# ProPrj_Smart_medcil_2024-12-30.net
KiCad netlist of a schematic drawn in EasyEDA Pro
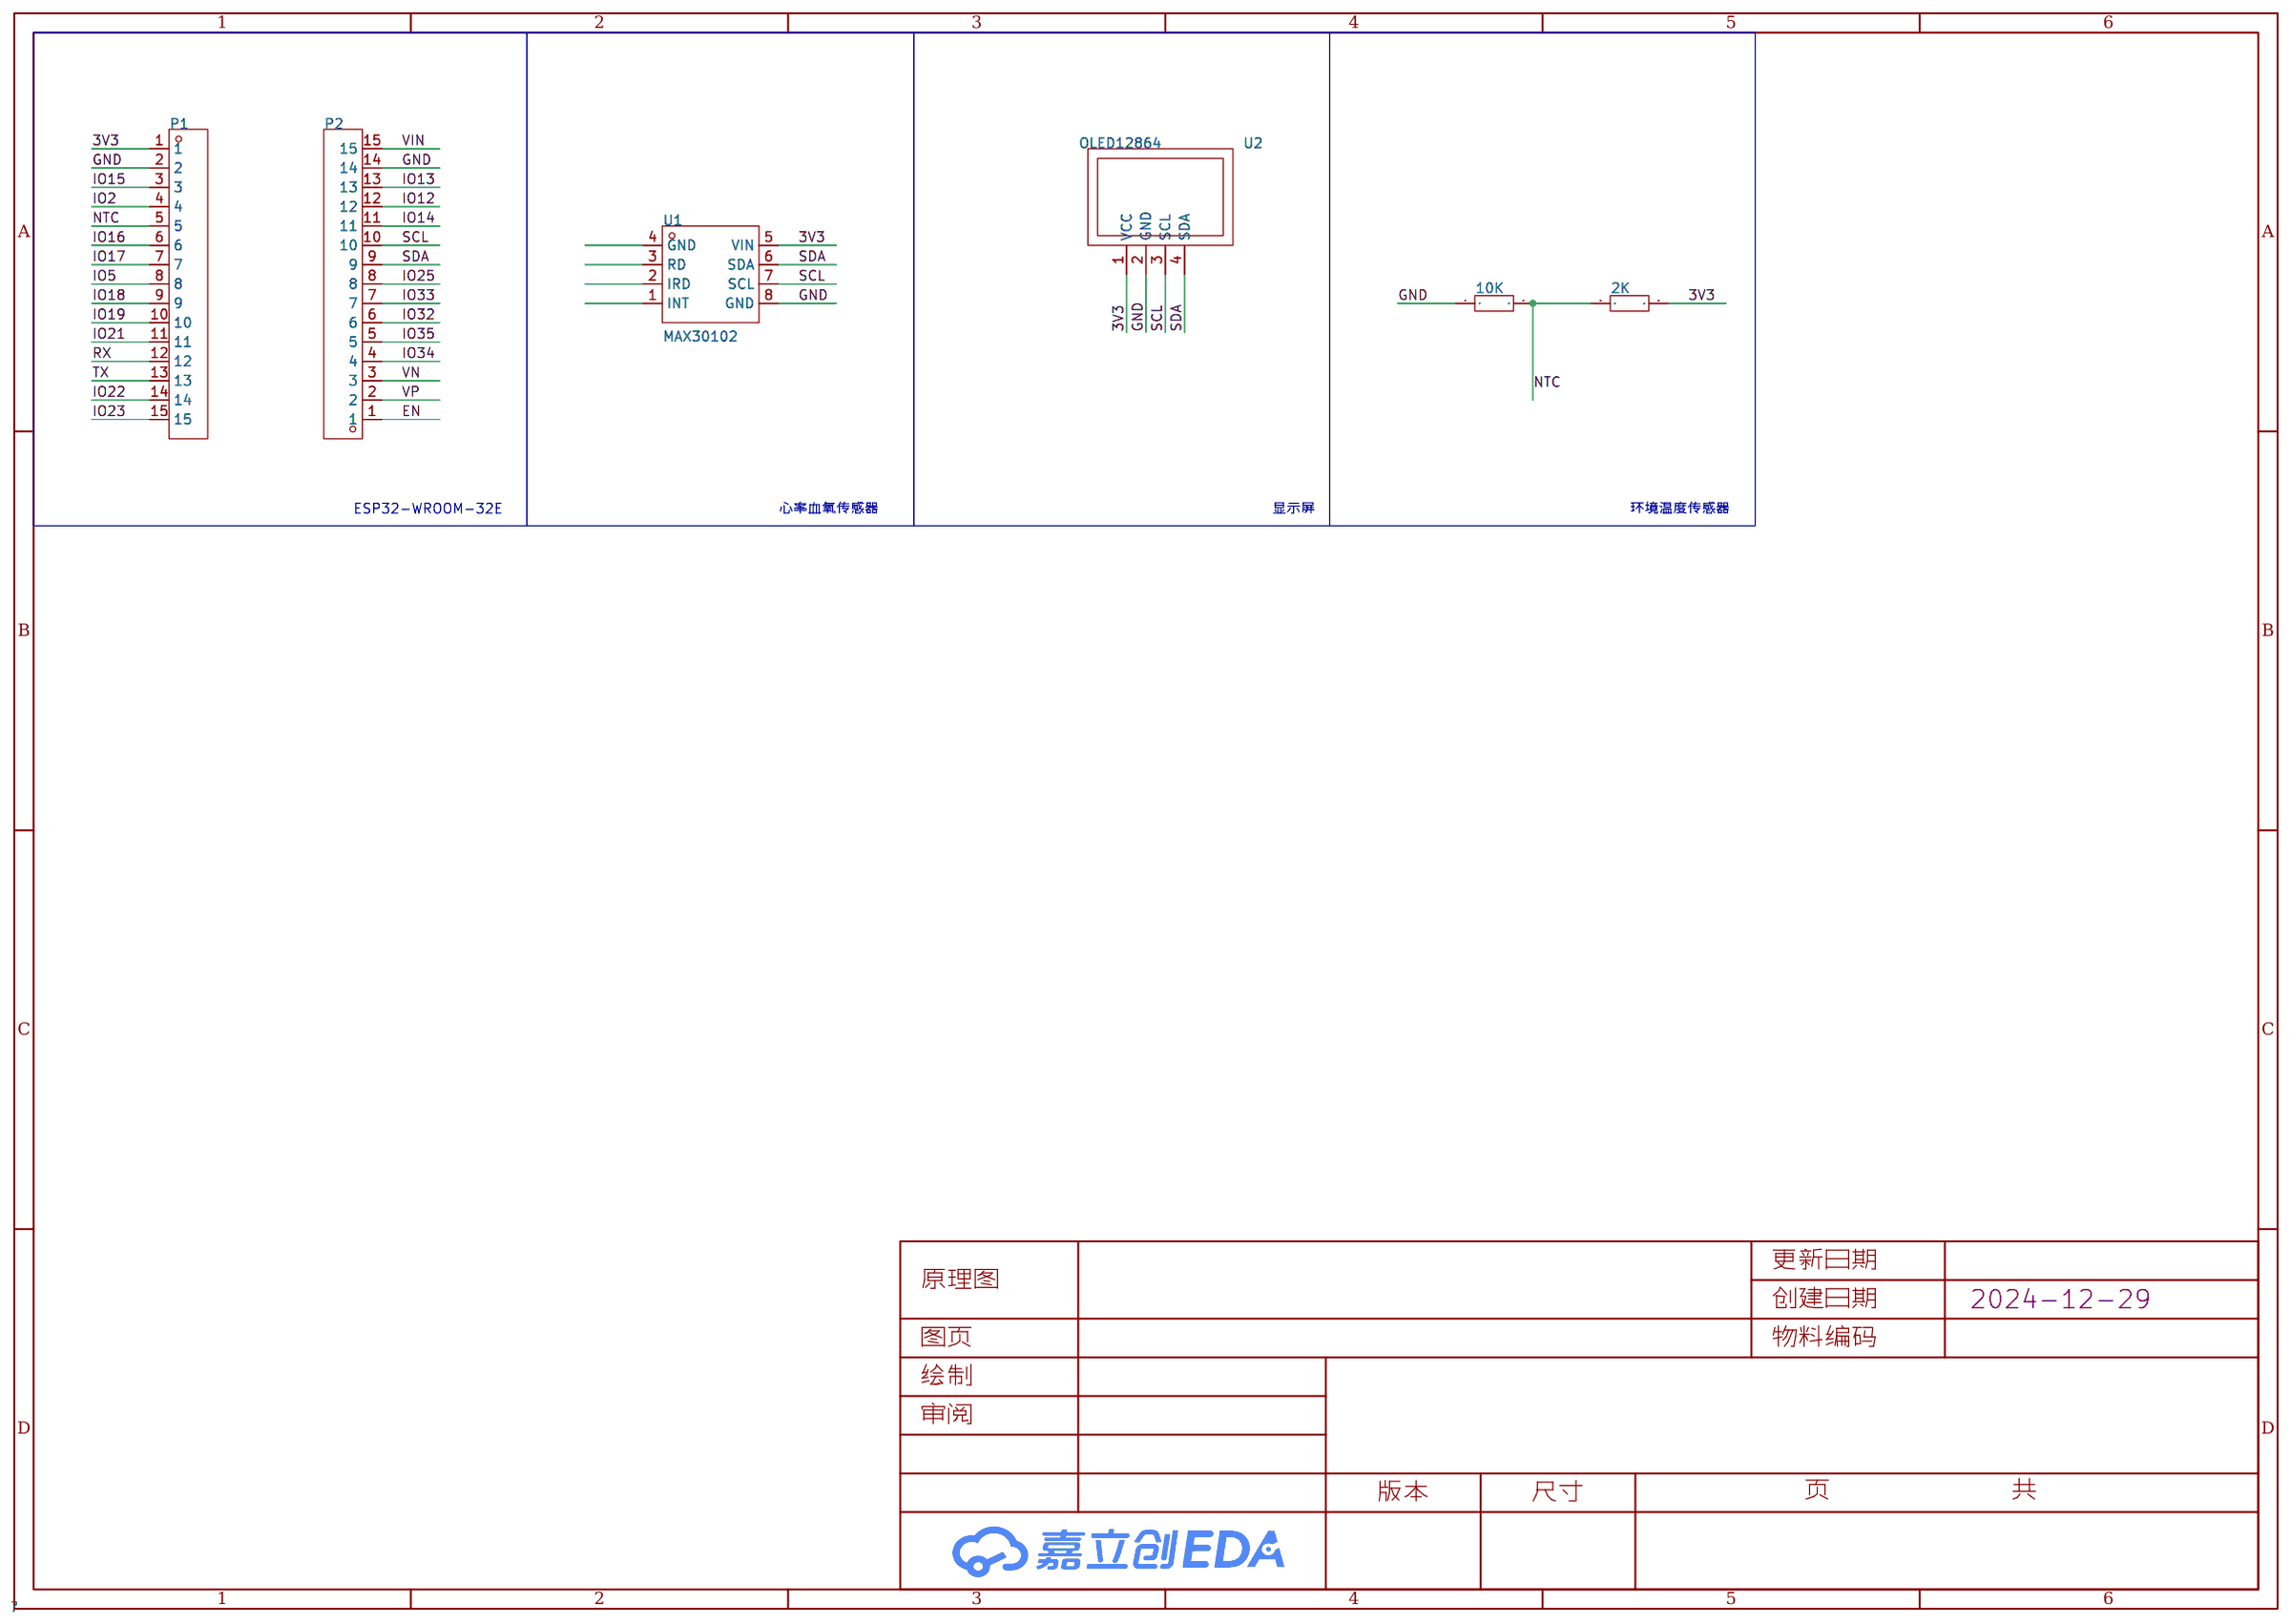
[diagram p0: schematic sheet]

(export (version "E")
  (design (tool "Eeschema 10.0.6"))
  (components
    (comp (ref "2K")
      (value "~")
      (footprint "easyedapro:RES-TH_BD2.3-L6.5-P10.50-D0.5")
      (libsource (lib "easyedapro") (part "CR-L3W-10ΩJ"))
    )
    (comp (ref "10K")
      (value "10K")
      (footprint "easyedapro:footprint_c2d9")
      (fields (field (name "Manufacturer Part") "0603WAF1002T5E") (field (name "Manufacturer") "UniOhm"))
      (libsource (lib "easyedapro") (part "10K"))
    )
    (comp (ref "P1")
      (value "排针15pin")
      (footprint "easyedapro:排针15PIN")
      (libsource (lib "easyedapro") (part "排针15pin"))
    )
    (comp (ref "P2")
      (value "排针15pin")
      (footprint "easyedapro:排针15PIN")
      (libsource (lib "easyedapro") (part "排针15pin"))
    )
    (comp (ref "U1")
      (value "MAX30102")
      (footprint "easyedapro:MAX30102")
      (libsource (lib "easyedapro") (part "MAX30102"))
    )
    (comp (ref "U2")
      (value "OLED12864")
      (footprint "easyedapro:OLED12864模块I2C")
      (libsource (lib "easyedapro") (part "OLED12864"))
    )
  )
  (nets
    (net (code "1") (name "/3V3") (class "Default")
      (node (ref "2K") (pin "2") (pinfunction "2_2") (pintype "unspecified"))
      (node (ref "P1") (pin "1") (pinfunction "1_1") (pintype "unspecified"))
      (node (ref "U1") (pin "5") (pinfunction "VIN_5") (pintype "input"))
      (node (ref "U2") (pin "1") (pinfunction "VCC_1") (pintype "unspecified"))
    )
    (net (code "2") (name "/EN") (class "Default")
      (node (ref "P2") (pin "1") (pinfunction "1_1") (pintype "unspecified"))
    )
    (net (code "3") (name "/GND") (class "Default")
      (node (ref "10K") (pin "1") (pinfunction "1_1") (pintype "input"))
      (node (ref "P1") (pin "2") (pinfunction "2_2") (pintype "unspecified"))
      (node (ref "P2") (pin "14") (pinfunction "14_14") (pintype "unspecified"))
      (node (ref "U1") (pin "8") (pinfunction "GND_8") (pintype "input"))
      (node (ref "U2") (pin "2") (pinfunction "GND_2") (pintype "unspecified"))
    )
    (net (code "4") (name "/IO2") (class "Default")
      (node (ref "P1") (pin "4") (pinfunction "4_4") (pintype "unspecified"))
    )
    (net (code "5") (name "/IO5") (class "Default")
      (node (ref "P1") (pin "8") (pinfunction "8_8") (pintype "unspecified"))
    )
    (net (code "6") (name "/IO12") (class "Default")
      (node (ref "P2") (pin "12") (pinfunction "12_12") (pintype "unspecified"))
    )
    (net (code "7") (name "/IO13") (class "Default")
      (node (ref "P2") (pin "13") (pinfunction "13_13") (pintype "unspecified"))
    )
    (net (code "8") (name "/IO14") (class "Default")
      (node (ref "P2") (pin "11") (pinfunction "11_11") (pintype "unspecified"))
    )
    (net (code "9") (name "/IO15") (class "Default")
      (node (ref "P1") (pin "3") (pinfunction "3_3") (pintype "unspecified"))
    )
    (net (code "10") (name "/IO16") (class "Default")
      (node (ref "P1") (pin "6") (pinfunction "6_6") (pintype "unspecified"))
    )
    (net (code "11") (name "/IO17") (class "Default")
      (node (ref "P1") (pin "7") (pinfunction "7_7") (pintype "unspecified"))
    )
    (net (code "12") (name "/IO18") (class "Default")
      (node (ref "P1") (pin "9") (pinfunction "9_9") (pintype "unspecified"))
    )
    (net (code "13") (name "/IO19") (class "Default")
      (node (ref "P1") (pin "10") (pinfunction "10_10") (pintype "unspecified"))
    )
    (net (code "14") (name "/IO21") (class "Default")
      (node (ref "P1") (pin "11") (pinfunction "11_11") (pintype "unspecified"))
    )
    (net (code "15") (name "/IO22") (class "Default")
      (node (ref "P1") (pin "14") (pinfunction "14_14") (pintype "unspecified"))
    )
    (net (code "16") (name "/IO23") (class "Default")
      (node (ref "P1") (pin "15") (pinfunction "15_15") (pintype "unspecified"))
    )
    (net (code "17") (name "/IO25") (class "Default")
      (node (ref "P2") (pin "8") (pinfunction "8_8") (pintype "unspecified"))
    )
    (net (code "18") (name "/IO32") (class "Default")
      (node (ref "P2") (pin "6") (pinfunction "6_6") (pintype "unspecified"))
    )
    (net (code "19") (name "/IO33") (class "Default")
      (node (ref "P2") (pin "7") (pinfunction "7_7") (pintype "unspecified"))
    )
    (net (code "20") (name "/IO34") (class "Default")
      (node (ref "P2") (pin "4") (pinfunction "4_4") (pintype "unspecified"))
    )
    (net (code "21") (name "/IO35") (class "Default")
      (node (ref "P2") (pin "5") (pinfunction "5_5") (pintype "unspecified"))
    )
    (net (code "22") (name "/NTC") (class "Default")
      (node (ref "10K") (pin "2") (pinfunction "2_2") (pintype "input"))
      (node (ref "2K") (pin "1") (pinfunction "1_1") (pintype "unspecified"))
      (node (ref "P1") (pin "5") (pinfunction "5_5") (pintype "unspecified"))
    )
    (net (code "23") (name "/RX") (class "Default")
      (node (ref "P1") (pin "12") (pinfunction "12_12") (pintype "unspecified"))
    )
    (net (code "24") (name "/SCL") (class "Default")
      (node (ref "P2") (pin "10") (pinfunction "10_10") (pintype "unspecified"))
      (node (ref "U1") (pin "7") (pinfunction "SCL_7") (pintype "input"))
      (node (ref "U2") (pin "3") (pinfunction "SCL_3") (pintype "unspecified"))
    )
    (net (code "25") (name "/SDA") (class "Default")
      (node (ref "P2") (pin "9") (pinfunction "9_9") (pintype "unspecified"))
      (node (ref "U1") (pin "6") (pinfunction "SDA_6") (pintype "input"))
      (node (ref "U2") (pin "4") (pinfunction "SDA_4") (pintype "unspecified"))
    )
    (net (code "26") (name "/TX") (class "Default")
      (node (ref "P1") (pin "13") (pinfunction "13_13") (pintype "unspecified"))
    )
    (net (code "27") (name "/VIN") (class "Default")
      (node (ref "P2") (pin "15") (pinfunction "15_15") (pintype "unspecified"))
    )
    (net (code "28") (name "/VN") (class "Default")
      (node (ref "P2") (pin "3") (pinfunction "3_3") (pintype "unspecified"))
    )
    (net (code "29") (name "/VP") (class "Default")
      (node (ref "P2") (pin "2") (pinfunction "2_2") (pintype "unspecified"))
    )
    (net (code "30") (name "unconnected-(U1-GND-Pad4)") (class "Default")
      (node (ref "U1") (pin "4") (pinfunction "GND_4") (pintype "input"))
    )
    (net (code "31") (name "unconnected-(U1-INT-Pad1)") (class "Default")
      (node (ref "U1") (pin "1") (pinfunction "INT_1") (pintype "input"))
    )
    (net (code "32") (name "unconnected-(U1-IRD-Pad2)") (class "Default")
      (node (ref "U1") (pin "2") (pinfunction "IRD_2") (pintype "input"))
    )
    (net (code "33") (name "unconnected-(U1-RD-Pad3)") (class "Default")
      (node (ref "U1") (pin "3") (pinfunction "RD_3") (pintype "input"))
    )
  )
)
